# Sheet-ThermalType-STM32.net
KiCad netlist of a schematic drawn in Altium Designer
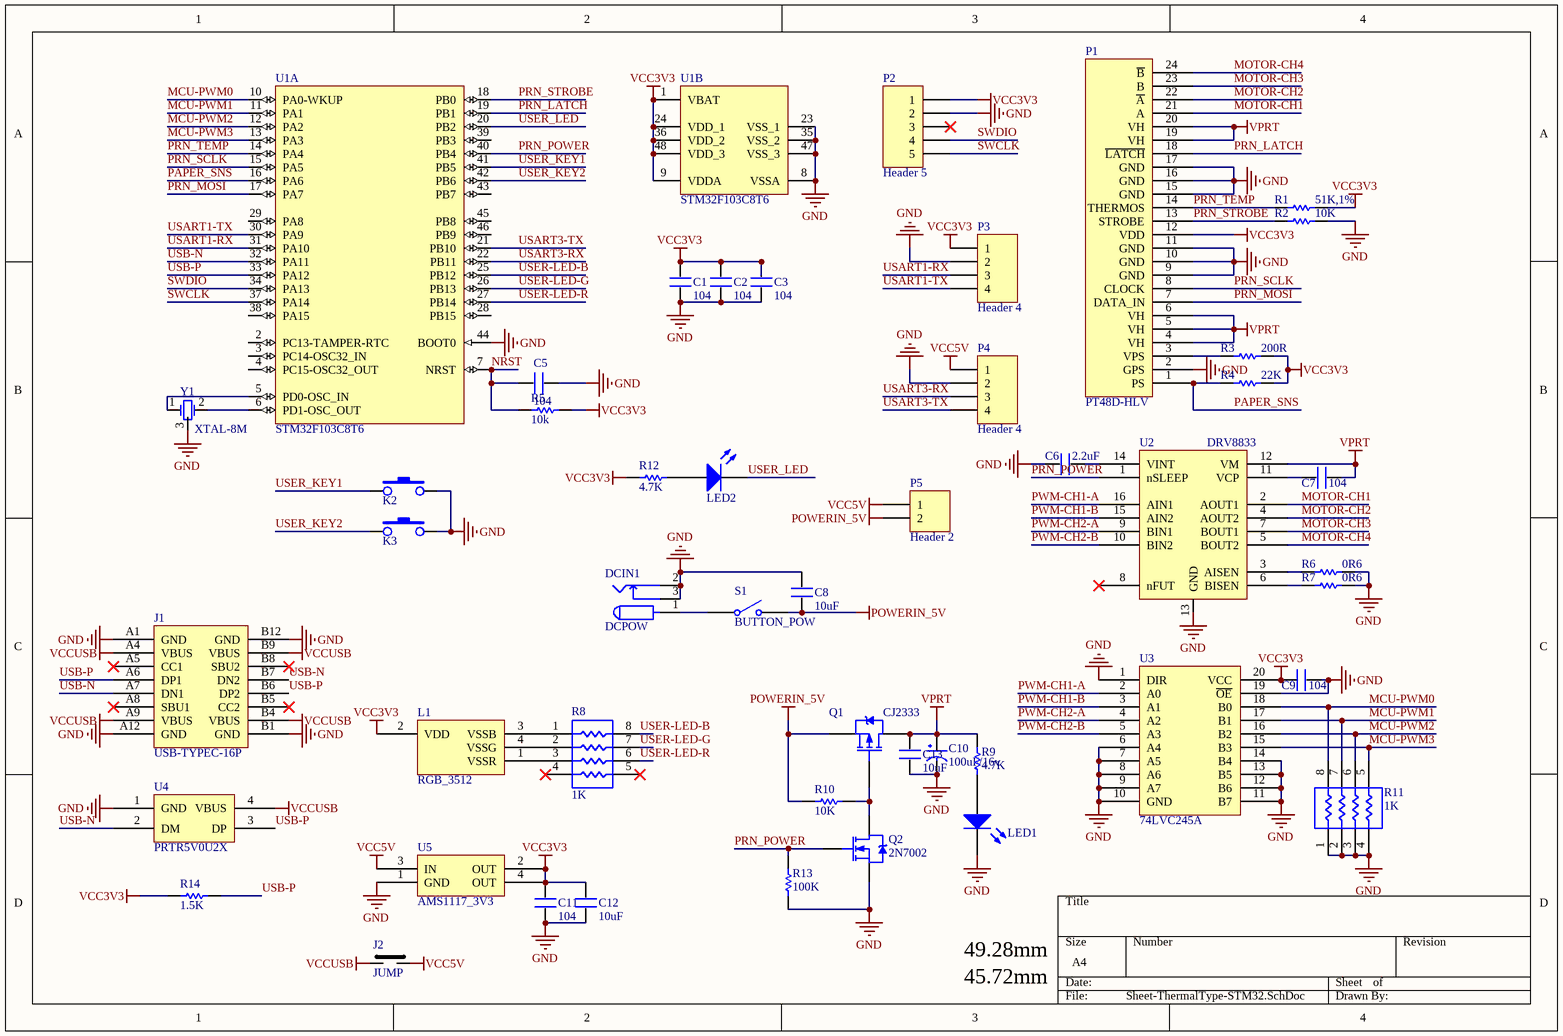
[diagram p0: Sheet-ThermalType-STM32.SchDoc]

(export (version "E")
  (design (tool "Eeschema 10.0.6"))
  (components
    (comp (ref "C1") (value "104") (footprint "0603c") (libsource (lib "Mlia") (part "0603c")))
    (comp (ref "C2") (value "104") (footprint "0603c") (libsource (lib "Mlia") (part "0603c")))
    (comp (ref "C3") (value "104") (footprint "0603c") (libsource (lib "Mlia") (part "0603c")))
    (comp (ref "C5") (value "104") (footprint "0603c") (libsource (lib "Mlia") (part "0603c")))
    (comp (ref "C6")
      (value "2.2uF")
      (footprint "0603C")
      (description "电容")
      (libsource (lib "Mlia") (part "0603C"))
    )
    (comp (ref "C7")
      (value "104")
      (footprint "0603C")
      (description "电容")
      (libsource (lib "Mlia") (part "0603C"))
    )
    (comp (ref "C8") (value "10uF") (footprint "0603C") (libsource (lib "Mlia") (part "0603C")))
    (comp (ref "C9")
      (value "104")
      (footprint "0603C")
      (description "电容")
      (libsource (lib "Mlia") (part "0603C"))
    )
    (comp (ref "C10")
      (value "100uF/16v")
      (footprint "ECAP_V")
      (description "电容")
      (libsource (lib "Mlia") (part "ECAP"))
    )
    (comp (ref "C11") (value "104") (footprint "0603C") (libsource (lib "Mlia") (part "0603C")))
    (comp (ref "C12") (value "10uF") (footprint "0603C") (libsource (lib "Mlia") (part "0603C")))
    (comp (ref "C13") (value "10uF") (footprint "0603C") (libsource (lib "Mlia") (part "0603C")))
    (comp (ref "DCIN1")
      (value "DCPOW")
      (footprint "DC10B")
      (description "DC电源头")
      (libsource (lib "Mlia") (part "DCPOW"))
    )
    (comp (ref "J1")
      (value "USB-TYPEC-16P")
      (footprint "USB-TYPEC-16P")
      (libsource (lib "Mlia") (part "USB-TYPEC-16P"))
    )
    (comp (ref "J2") (value "JUMP") (footprint "JUMP") (libsource (lib "Mlia") (part "JUMP")))
    (comp (ref "K2")
      (value "侧脚6*6*X微动按键")
      (footprint "侧脚6*6*X微动按键")
      (libsource (lib "Mlia") (part "侧脚6*6*X微动按键"))
    )
    (comp (ref "K3")
      (value "侧脚6*6*X微动按键")
      (footprint "侧脚6*6*X微动按键")
      (libsource (lib "Mlia") (part "侧脚6*6*X微动按键"))
    )
    (comp (ref "L1") (value "RGB_3512") (footprint "RGB_3528") (libsource (lib "Mlia") (part "RGB_3512")))
    (comp (ref "LED1") (value "0603LED") (footprint "0603LED") (libsource (lib "Mlia") (part "0603LED")))
    (comp (ref "LED2") (value "0603LED") (footprint "0603LED") (libsource (lib "Mlia") (part "0603LED")))
    (comp (ref "P1")
      (value "PT48D-HLV")
      (footprint "_FPC_24P_0.5MM")
      (libsource (lib "Mlia") (part "PT48D-HLV"))
    )
    (comp (ref "P2")
      (value "Header 5")
      (footprint "sh1.25_LT_5P")
      (description "Header, 5-Pin")
      (fields (field (name "PUBLISHER") "Altium Limited"))
      (libsource (lib "Miscellaneous Connectors") (part "Header 5"))
    )
    (comp (ref "P3")
      (value "Header 4")
      (footprint "SH1.25_LT_4P")
      (description "Header, 4-Pin")
      (fields (field (name "PUBLISHER") "Altium Limited"))
      (libsource (lib "Miscellaneous Connectors") (part "Header 4"))
    )
    (comp (ref "P4")
      (value "Header 4")
      (footprint "SH1.25_LT_4P")
      (description "Header, 4-Pin")
      (fields (field (name "PUBLISHER") "Altium Limited"))
      (libsource (lib "Miscellaneous Connectors") (part "Header 4"))
    )
    (comp (ref "P5")
      (value "Header 2")
      (footprint "HDR1X2")
      (description "Header, 2-Pin")
      (fields (field (name "PUBLISHER") "Altium Limited"))
      (libsource (lib "Miscellaneous Connectors") (part "Header 2"))
    )
    (comp (ref "Q1")
      (value "CJ2333")
      (footprint "CJ2333")
      (description "P-MOS")
      (libsource (lib "Mlia") (part "CJ2333"))
    )
    (comp (ref "Q2")
      (value "2N7002")
      (footprint "2N7002")
      (description "N-Channel Power MOSFET")
      (fields (field (name "PUBLISHER") "Altium Limited"))
      (libsource (lib "Mlia") (part "NMOS-2"))
    )
    (comp (ref "R1")
      (value "51K,1%")
      (footprint "0603r")
      (description "电阻")
      (libsource (lib "Mlia") (part "0603R"))
    )
    (comp (ref "R2")
      (value "10K")
      (footprint "0603r")
      (description "电阻")
      (libsource (lib "Mlia") (part "0603R"))
    )
    (comp (ref "R3")
      (value "200R")
      (footprint "0603r")
      (description "电阻")
      (libsource (lib "Mlia") (part "0603R"))
    )
    (comp (ref "R4")
      (value "22K")
      (footprint "0603r")
      (description "电阻")
      (libsource (lib "Mlia") (part "0603R"))
    )
    (comp (ref "R5") (value "10k") (footprint "0603r") (libsource (lib "Mlia") (part "0603r")))
    (comp (ref "R6")
      (value "0R6")
      (footprint "0805R")
      (description "电阻")
      (libsource (lib "Mlia") (part "0805R"))
    )
    (comp (ref "R7")
      (value "0R6")
      (footprint "0805R")
      (description "电阻")
      (libsource (lib "Mlia") (part "0805R"))
    )
    (comp (ref "R8") (value "1K") (footprint "0603RES") (libsource (lib "Mlia") (part "0603RES")))
    (comp (ref "R9") (value "4.7K") (footprint "0603r") (libsource (lib "Mlia") (part "0603R")))
    (comp (ref "R10")
      (value "10K")
      (footprint "0603r")
      (description "电阻")
      (libsource (lib "Mlia") (part "0603R"))
    )
    (comp (ref "R11")
      (value "1K")
      (footprint "0603RES")
      (description "排阻")
      (libsource (lib "Mlia") (part "0603RES"))
    )
    (comp (ref "R12") (value "4.7K") (footprint "0603r") (libsource (lib "Mlia") (part "0603R")))
    (comp (ref "R13")
      (value "100K")
      (footprint "0603r")
      (description "电阻")
      (libsource (lib "Mlia") (part "0603R"))
    )
    (comp (ref "R14") (value "1.5K") (footprint "0603r") (libsource (lib "Mlia") (part "0603R")))
    (comp (ref "S1") (value "BUTTON_POW") (footprint "拨动开关SS-12D") (libsource (lib "Mlia") (part "自锁开关")))
    (comp (ref "U1")
      (value "STM32F103C8T6")
      (footprint "STM-LQFP48-L")
      (libsource (lib "STMicroelectronics STM32 F1") (part "STM32F103C8T6"))
    )
    (comp (ref "U2") (value "DRV8833") (footprint "DRV8833") (libsource (lib "Mlia") (part "DRV8833")))
    (comp (ref "U3")
      (value "74LVC245A")
      (footprint "Mlia:TSSOP20")
      (description "8通道隔离芯片")
      (libsource (lib "Mlia") (part "74LVC245A"))
    )
    (comp (ref "U4")
      (value "PRTR5V0U2X")
      (footprint "SOT-143")
      (description "超低容值轨对轨静电放电保护二极管,主要保护两条高速数据或者高频率信号线免受静电放电和其他瞬变的影响")
      (libsource (lib "Mlia") (part "PRTR5V0U2X"))
    )
    (comp (ref "U5")
      (value "AMS1117_3V3")
      (footprint "AMS1117_SOT223")
      (libsource (lib "Mlia") (part "AMS1117"))
    )
    (comp (ref "Y1")
      (value "XTAL-8M")
      (footprint "XTAL_8M")
      (description "晶振")
      (libsource (lib "Mlia") (part "XTAL-8M"))
    )
  )
  (nets
    (net (code "1") (name "/MCU-PWM0") (class "Default")
      (node (ref "R11") (pin "8") (pinfunction "8_8") (pintype "passive"))
      (node (ref "U1") (pin "10") (pinfunction "PA0-WKUP_10") (pintype "bidirectional"))
      (node (ref "U3") (pin "18") (pinfunction "B0_18") (pintype "passive"))
    )
    (net (code "2") (name "/MCU-PWM1") (class "Default")
      (node (ref "R11") (pin "7") (pinfunction "7_7") (pintype "passive"))
      (node (ref "U1") (pin "11") (pinfunction "PA1_11") (pintype "bidirectional"))
      (node (ref "U3") (pin "17") (pinfunction "B1_17") (pintype "passive"))
    )
    (net (code "3") (name "/MCU-PWM2") (class "Default")
      (node (ref "R11") (pin "6") (pinfunction "6_6") (pintype "passive"))
      (node (ref "U1") (pin "12") (pinfunction "PA2_12") (pintype "bidirectional"))
      (node (ref "U3") (pin "16") (pinfunction "B2_16") (pintype "passive"))
    )
    (net (code "4") (name "/MCU-PWM3") (class "Default")
      (node (ref "R11") (pin "5") (pinfunction "5_5") (pintype "passive"))
      (node (ref "U1") (pin "13") (pinfunction "PA3_13") (pintype "bidirectional"))
      (node (ref "U3") (pin "15") (pinfunction "B3_15") (pintype "passive"))
    )
    (net (code "5") (name "/MOTOR-CH1") (class "Default")
      (node (ref "P1") (pin "21") (pinfunction "A_21") (pintype "passive"))
      (node (ref "U2") (pin "2") (pinfunction "AOUT1_2") (pintype "passive"))
    )
    (net (code "6") (name "/MOTOR-CH2") (class "Default")
      (node (ref "P1") (pin "22") (pinfunction "~{A}_22") (pintype "passive"))
      (node (ref "U2") (pin "4") (pinfunction "AOUT2_4") (pintype "passive"))
    )
    (net (code "7") (name "/MOTOR-CH3") (class "Default")
      (node (ref "P1") (pin "23") (pinfunction "B_23") (pintype "passive"))
      (node (ref "U2") (pin "7") (pinfunction "BOUT1_7") (pintype "passive"))
    )
    (net (code "8") (name "/MOTOR-CH4") (class "Default")
      (node (ref "P1") (pin "24") (pinfunction "~{B}_24") (pintype "passive"))
      (node (ref "U2") (pin "5") (pinfunction "BOUT2_5") (pintype "passive"))
    )
    (net (code "9") (name "/NRST") (class "Default")
      (node (ref "C5") (pin "1") (pintype "passive"))
      (node (ref "R5") (pin "1") (pinfunction "1_1") (pintype "passive"))
      (node (ref "U1") (pin "7") (pinfunction "NRST_7") (pintype "bidirectional"))
    )
    (net (code "10") (name "/PAPER_SNS") (class "Default")
      (node (ref "P1") (pin "1") (pinfunction "PS_1") (pintype "passive"))
      (node (ref "R4") (pin "1") (pinfunction "1_1") (pintype "passive"))
      (node (ref "U1") (pin "16") (pinfunction "PA6_16") (pintype "bidirectional"))
    )
    (net (code "11") (name "/PRN_LATCH") (class "Default")
      (node (ref "P1") (pin "18") (pinfunction "~{LATCH}_18") (pintype "passive"))
      (node (ref "U1") (pin "19") (pinfunction "PB1_19") (pintype "bidirectional"))
    )
    (net (code "12") (name "/PRN_MOSI") (class "Default")
      (node (ref "P1") (pin "7") (pinfunction "DATA_IN_7") (pintype "passive"))
      (node (ref "U1") (pin "17") (pinfunction "PA7_17") (pintype "bidirectional"))
    )
    (net (code "13") (name "/PRN_POWER") (class "Default")
      (node (ref "Q2") (pin "1") (pinfunction "G_1") (pintype "passive"))
      (node (ref "R13") (pin "2") (pinfunction "2_2") (pintype "passive"))
      (node (ref "U1") (pin "40") (pinfunction "PB4_40") (pintype "bidirectional"))
      (node (ref "U2") (pin "1") (pinfunction "nSLEEP_1") (pintype "passive"))
    )
    (net (code "14") (name "/PRN_SCLK") (class "Default")
      (node (ref "P1") (pin "8") (pinfunction "CLOCK_8") (pintype "passive"))
      (node (ref "U1") (pin "15") (pinfunction "PA5_15") (pintype "bidirectional"))
    )
    (net (code "15") (name "/PRN_STROBE") (class "Default")
      (node (ref "P1") (pin "13") (pinfunction "STROBE_13") (pintype "passive"))
      (node (ref "R2") (pin "1") (pinfunction "1_1") (pintype "passive"))
      (node (ref "U1") (pin "18") (pinfunction "PB0_18") (pintype "bidirectional"))
    )
    (net (code "16") (name "/PRN_TEMP") (class "Default")
      (node (ref "P1") (pin "14") (pinfunction "THERMOS_14") (pintype "passive"))
      (node (ref "R1") (pin "1") (pinfunction "1_1") (pintype "passive"))
      (node (ref "U1") (pin "14") (pinfunction "PA4_14") (pintype "bidirectional"))
    )
    (net (code "17") (name "/PWM-CH1-A") (class "Default")
      (node (ref "U2") (pin "16") (pinfunction "AIN1_16") (pintype "passive"))
      (node (ref "U3") (pin "2") (pinfunction "A0_2") (pintype "passive"))
    )
    (net (code "18") (name "/PWM-CH1-B") (class "Default")
      (node (ref "U2") (pin "15") (pinfunction "AIN2_15") (pintype "passive"))
      (node (ref "U3") (pin "3") (pinfunction "A1_3") (pintype "passive"))
    )
    (net (code "19") (name "/PWM-CH2-A") (class "Default")
      (node (ref "U2") (pin "9") (pinfunction "BIN1_9") (pintype "passive"))
      (node (ref "U3") (pin "4") (pinfunction "A2_4") (pintype "passive"))
    )
    (net (code "20") (name "/PWM-CH2-B") (class "Default")
      (node (ref "U2") (pin "10") (pinfunction "BIN2_10") (pintype "passive"))
      (node (ref "U3") (pin "5") (pinfunction "A3_5") (pintype "passive"))
    )
    (net (code "21") (name "/SWCLK") (class "Default")
      (node (ref "P2") (pin "5") (pinfunction "5_5") (pintype "passive"))
      (node (ref "U1") (pin "37") (pinfunction "PA14_37") (pintype "bidirectional"))
    )
    (net (code "22") (name "/SWDIO") (class "Default")
      (node (ref "P2") (pin "4") (pinfunction "4_4") (pintype "passive"))
      (node (ref "U1") (pin "34") (pinfunction "PA13_34") (pintype "bidirectional"))
    )
    (net (code "23") (name "/USART1-RX") (class "Default")
      (node (ref "P3") (pin "3") (pinfunction "3_3") (pintype "passive"))
      (node (ref "U1") (pin "31") (pinfunction "PA10_31") (pintype "bidirectional"))
    )
    (net (code "24") (name "/USART1-TX") (class "Default")
      (node (ref "P3") (pin "4") (pinfunction "4_4") (pintype "passive"))
      (node (ref "U1") (pin "30") (pinfunction "PA9_30") (pintype "bidirectional"))
    )
    (net (code "25") (name "/USART3-RX") (class "Default")
      (node (ref "P4") (pin "3") (pinfunction "3_3") (pintype "passive"))
      (node (ref "U1") (pin "22") (pinfunction "PB11_22") (pintype "bidirectional"))
    )
    (net (code "26") (name "/USART3-TX") (class "Default")
      (node (ref "P4") (pin "4") (pinfunction "4_4") (pintype "passive"))
      (node (ref "U1") (pin "21") (pinfunction "PB10_21") (pintype "bidirectional"))
    )
    (net (code "27") (name "/USB-N") (class "Default")
      (node (ref "J1") (pin "A7") (pinfunction "DN1_A7") (pintype "passive"))
      (node (ref "J1") (pin "B7") (pinfunction "DN2_B7") (pintype "passive"))
      (node (ref "U1") (pin "32") (pinfunction "PA11_32") (pintype "bidirectional"))
      (node (ref "U4") (pin "2") (pinfunction "DM_2") (pintype "passive"))
    )
    (net (code "28") (name "/USB-P") (class "Default")
      (node (ref "J1") (pin "A6") (pinfunction "DP1_A6") (pintype "passive"))
      (node (ref "J1") (pin "B6") (pinfunction "DP2_B6") (pintype "passive"))
      (node (ref "R14") (pin "2") (pinfunction "2_2") (pintype "passive"))
      (node (ref "U1") (pin "33") (pinfunction "PA12_33") (pintype "bidirectional"))
      (node (ref "U4") (pin "3") (pinfunction "DP_3") (pintype "passive"))
    )
    (net (code "29") (name "/USER-LED-B") (class "Default")
      (node (ref "R8") (pin "8") (pinfunction "8_8") (pintype "passive"))
      (node (ref "U1") (pin "25") (pinfunction "PB12_25") (pintype "bidirectional"))
    )
    (net (code "30") (name "/USER-LED-G") (class "Default")
      (node (ref "R8") (pin "7") (pinfunction "7_7") (pintype "passive"))
      (node (ref "U1") (pin "26") (pinfunction "PB13_26") (pintype "bidirectional"))
    )
    (net (code "31") (name "/USER-LED-R") (class "Default")
      (node (ref "R8") (pin "6") (pinfunction "6_6") (pintype "passive"))
      (node (ref "U1") (pin "27") (pinfunction "PB14_27") (pintype "bidirectional"))
    )
    (net (code "32") (name "/USER_KEY1") (class "Default")
      (node (ref "K2") (pin "2") (pinfunction "2_2") (pintype "passive"))
      (node (ref "U1") (pin "41") (pinfunction "PB5_41") (pintype "bidirectional"))
    )
    (net (code "33") (name "/USER_KEY2") (class "Default")
      (node (ref "K3") (pin "2") (pinfunction "2_2") (pintype "passive"))
      (node (ref "U1") (pin "42") (pinfunction "PB6_42") (pintype "bidirectional"))
    )
    (net (code "34") (name "/USER_LED") (class "Default")
      (node (ref "LED2") (pin "2") (pinfunction "K_2") (pintype "passive"))
      (node (ref "U1") (pin "20") (pinfunction "PB2_20") (pintype "bidirectional"))
    )
    (net (code "35") (name "GND") (class "Default")
      (node (ref "C1") (pin "1") (pintype "passive"))
      (node (ref "C10") (pin "2") (pinfunction "GND_2") (pintype "passive"))
      (node (ref "C11") (pin "1") (pintype "passive"))
      (node (ref "C12") (pin "1") (pintype "passive"))
      (node (ref "C13") (pin "1") (pintype "passive"))
      (node (ref "C2") (pin "1") (pintype "passive"))
      (node (ref "C3") (pin "1") (pintype "passive"))
      (node (ref "C5") (pin "2") (pintype "passive"))
      (node (ref "C6") (pin "1") (pintype "passive"))
      (node (ref "C8") (pin "2") (pintype "passive"))
      (node (ref "C9") (pin "2") (pintype "passive"))
      (node (ref "DCIN1") (pin "2") (pintype "passive"))
      (node (ref "DCIN1") (pin "3") (pintype "passive"))
      (node (ref "J1") (pin "A1") (pinfunction "GND_A1") (pintype "passive"))
      (node (ref "J1") (pin "A12") (pinfunction "GND_A12") (pintype "passive"))
      (node (ref "J1") (pin "B1") (pinfunction "GND_B1") (pintype "passive"))
      (node (ref "J1") (pin "B12") (pinfunction "GND_B12") (pintype "passive"))
      (node (ref "K2") (pin "1") (pinfunction "1_1") (pintype "passive"))
      (node (ref "K3") (pin "1") (pinfunction "1_1") (pintype "passive"))
      (node (ref "LED1") (pin "2") (pinfunction "K_2") (pintype "passive"))
      (node (ref "P1") (pin "10") (pinfunction "GND_10") (pintype "passive"))
      (node (ref "P1") (pin "11") (pinfunction "GND_11") (pintype "passive"))
      (node (ref "P1") (pin "15") (pinfunction "GND_15") (pintype "passive"))
      (node (ref "P1") (pin "16") (pinfunction "GND_16") (pintype "passive"))
      (node (ref "P1") (pin "17") (pinfunction "GND_17") (pintype "passive"))
      (node (ref "P1") (pin "2") (pinfunction "GPS_2") (pintype "passive"))
      (node (ref "P1") (pin "9") (pinfunction "GND_9") (pintype "passive"))
      (node (ref "P2") (pin "2") (pinfunction "2_2") (pintype "passive"))
      (node (ref "P3") (pin "2") (pinfunction "2_2") (pintype "passive"))
      (node (ref "P4") (pin "2") (pinfunction "2_2") (pintype "passive"))
      (node (ref "Q2") (pin "2") (pinfunction "S_2") (pintype "passive"))
      (node (ref "R11") (pin "1") (pinfunction "1_1") (pintype "passive"))
      (node (ref "R11") (pin "2") (pinfunction "2_2") (pintype "passive"))
      (node (ref "R11") (pin "3") (pinfunction "3_3") (pintype "passive"))
      (node (ref "R11") (pin "4") (pinfunction "4_4") (pintype "passive"))
      (node (ref "R13") (pin "1") (pinfunction "1_1") (pintype "passive"))
      (node (ref "R2") (pin "2") (pinfunction "2_2") (pintype "passive"))
      (node (ref "R6") (pin "2") (pinfunction "2_2") (pintype "passive"))
      (node (ref "R7") (pin "2") (pinfunction "2_2") (pintype "passive"))
      (node (ref "U1") (pin "23") (pinfunction "VSS_1_23") (pintype "power_in"))
      (node (ref "U1") (pin "35") (pinfunction "VSS_2_35") (pintype "power_in"))
      (node (ref "U1") (pin "44") (pinfunction "BOOT0_44") (pintype "input"))
      (node (ref "U1") (pin "47") (pinfunction "VSS_3_47") (pintype "power_in"))
      (node (ref "U1") (pin "8") (pinfunction "VSSA_8") (pintype "power_in"))
      (node (ref "U2") (pin "13") (pinfunction "GND_13") (pintype "passive"))
      (node (ref "U3") (pin "1") (pinfunction "DIR_1") (pintype "passive"))
      (node (ref "U3") (pin "10") (pinfunction "GND_10") (pintype "passive"))
      (node (ref "U3") (pin "11") (pinfunction "B7_11") (pintype "passive"))
      (node (ref "U3") (pin "12") (pinfunction "B6_12") (pintype "passive"))
      (node (ref "U3") (pin "13") (pinfunction "B5_13") (pintype "passive"))
      (node (ref "U3") (pin "14") (pinfunction "B4_14") (pintype "passive"))
      (node (ref "U3") (pin "19") (pinfunction "~{OE}_19") (pintype "passive"))
      (node (ref "U3") (pin "6") (pinfunction "A4_6") (pintype "passive"))
      (node (ref "U3") (pin "7") (pinfunction "A5_7") (pintype "passive"))
      (node (ref "U3") (pin "8") (pinfunction "A6_8") (pintype "passive"))
      (node (ref "U3") (pin "9") (pinfunction "A7_9") (pintype "passive"))
      (node (ref "U4") (pin "1") (pinfunction "GND_1") (pintype "passive"))
      (node (ref "U5") (pin "1") (pinfunction "GND_1") (pintype "passive"))
      (node (ref "Y1") (pin "3") (pinfunction "3_3") (pintype "passive"))
    )
    (net (code "36") (name "Net-(L1-VSSB)") (class "Default")
      (node (ref "L1") (pin "3") (pinfunction "VSSB_3") (pintype "passive"))
      (node (ref "R8") (pin "1") (pinfunction "1_1") (pintype "passive"))
    )
    (net (code "37") (name "Net-(L1-VSSG)") (class "Default")
      (node (ref "L1") (pin "4") (pinfunction "VSSG_4") (pintype "passive"))
      (node (ref "R8") (pin "2") (pinfunction "2_2") (pintype "passive"))
    )
    (net (code "38") (name "Net-(L1-VSSR)") (class "Default")
      (node (ref "L1") (pin "1") (pinfunction "VSSR_1") (pintype "passive"))
      (node (ref "R8") (pin "3") (pinfunction "3_3") (pintype "passive"))
    )
    (net (code "39") (name "Net-(LED1-A)") (class "Default")
      (node (ref "LED1") (pin "1") (pinfunction "A_1") (pintype "passive"))
      (node (ref "R9") (pin "1") (pinfunction "1_1") (pintype "passive"))
    )
    (net (code "40") (name "Net-(LED2-A)") (class "Default")
      (node (ref "LED2") (pin "1") (pinfunction "A_1") (pintype "passive"))
      (node (ref "R12") (pin "1") (pinfunction "1_1") (pintype "passive"))
    )
    (net (code "41") (name "Net-(P1-VPS)") (class "Default")
      (node (ref "P1") (pin "3") (pinfunction "VPS_3") (pintype "passive"))
      (node (ref "R3") (pin "1") (pinfunction "1_1") (pintype "passive"))
    )
    (net (code "42") (name "Net-(Q1-G)") (class "Default")
      (node (ref "Q1") (pin "1") (pinfunction "G_1") (pintype "passive"))
      (node (ref "Q2") (pin "3") (pinfunction "D_3") (pintype "passive"))
      (node (ref "R10") (pin "2") (pinfunction "2_2") (pintype "passive"))
    )
    (net (code "43") (name "Net-(S1-COMMON)") (class "Default")
      (node (ref "DCIN1") (pin "1") (pintype "passive"))
      (node (ref "S1") (pin "2") (pinfunction "COMMON_2") (pintype "passive"))
    )
    (net (code "44") (name "Net-(U1A-PD0-OSC_IN)") (class "Default")
      (node (ref "U1") (pin "5") (pinfunction "PD0-OSC_IN_5") (pintype "bidirectional"))
      (node (ref "Y1") (pin "1") (pinfunction "OSC1_1") (pintype "passive"))
    )
    (net (code "45") (name "Net-(U1A-PD1-OSC_OUT)") (class "Default")
      (node (ref "U1") (pin "6") (pinfunction "PD1-OSC_OUT_6") (pintype "bidirectional"))
      (node (ref "Y1") (pin "2") (pinfunction "OSC2_2") (pintype "passive"))
    )
    (net (code "46") (name "Net-(U2-AISEN)") (class "Default")
      (node (ref "R6") (pin "1") (pinfunction "1_1") (pintype "passive"))
      (node (ref "U2") (pin "3") (pinfunction "AISEN_3") (pintype "passive"))
    )
    (net (code "47") (name "Net-(U2-BISEN)") (class "Default")
      (node (ref "R7") (pin "1") (pinfunction "1_1") (pintype "passive"))
      (node (ref "U2") (pin "6") (pinfunction "BISEN_6") (pintype "passive"))
    )
    (net (code "48") (name "Net-(U2-VCP)") (class "Default")
      (node (ref "C7") (pin "1") (pintype "passive"))
      (node (ref "U2") (pin "11") (pinfunction "VCP_11") (pintype "passive"))
    )
    (net (code "49") (name "Net-(U2-VINT)") (class "Default")
      (node (ref "C6") (pin "2") (pintype "passive"))
      (node (ref "U2") (pin "14") (pinfunction "VINT_14") (pintype "passive"))
    )
    (net (code "50") (name "POWERIN_5V") (class "Default")
      (node (ref "C8") (pin "1") (pintype "passive"))
      (node (ref "P5") (pin "2") (pinfunction "2_2") (pintype "passive"))
      (node (ref "Q1") (pin "3") (pinfunction "S_3") (pintype "passive"))
      (node (ref "R10") (pin "1") (pinfunction "1_1") (pintype "passive"))
      (node (ref "S1") (pin "3") (pinfunction "NO_3") (pintype "passive"))
    )
    (net (code "51") (name "VCC3V3") (class "Default")
      (node (ref "C1") (pin "2") (pintype "passive"))
      (node (ref "C11") (pin "2") (pintype "passive"))
      (node (ref "C12") (pin "2") (pintype "passive"))
      (node (ref "C2") (pin "2") (pintype "passive"))
      (node (ref "C3") (pin "2") (pintype "passive"))
      (node (ref "C9") (pin "1") (pintype "passive"))
      (node (ref "L1") (pin "2") (pinfunction "VDD_2") (pintype "passive"))
      (node (ref "P1") (pin "12") (pinfunction "VDD_12") (pintype "passive"))
      (node (ref "P2") (pin "1") (pinfunction "1_1") (pintype "passive"))
      (node (ref "P3") (pin "1") (pinfunction "1_1") (pintype "passive"))
      (node (ref "R1") (pin "2") (pinfunction "2_2") (pintype "passive"))
      (node (ref "R12") (pin "2") (pinfunction "2_2") (pintype "passive"))
      (node (ref "R14") (pin "1") (pinfunction "1_1") (pintype "passive"))
      (node (ref "R3") (pin "2") (pinfunction "2_2") (pintype "passive"))
      (node (ref "R4") (pin "2") (pinfunction "2_2") (pintype "passive"))
      (node (ref "R5") (pin "2") (pinfunction "2_2") (pintype "passive"))
      (node (ref "U1") (pin "1") (pinfunction "VBAT_1") (pintype "power_in"))
      (node (ref "U1") (pin "24") (pinfunction "VDD_1_24") (pintype "power_in"))
      (node (ref "U1") (pin "36") (pinfunction "VDD_2_36") (pintype "power_in"))
      (node (ref "U1") (pin "48") (pinfunction "VDD_3_48") (pintype "power_in"))
      (node (ref "U1") (pin "9") (pinfunction "VDDA_9") (pintype "power_in"))
      (node (ref "U3") (pin "20") (pinfunction "VCC_20") (pintype "passive"))
      (node (ref "U5") (pin "2") (pinfunction "OUT_2") (pintype "passive"))
      (node (ref "U5") (pin "4") (pinfunction "OUT_4") (pintype "passive"))
    )
    (net (code "52") (name "VCC5V") (class "Default")
      (node (ref "J2") (pin "2") (pinfunction "2_2") (pintype "passive"))
      (node (ref "P4") (pin "1") (pinfunction "1_1") (pintype "passive"))
      (node (ref "P5") (pin "1") (pinfunction "1_1") (pintype "passive"))
      (node (ref "U5") (pin "3") (pinfunction "IN_3") (pintype "passive"))
    )
    (net (code "53") (name "VCCUSB") (class "Default")
      (node (ref "J1") (pin "A4") (pinfunction "VBUS_A4") (pintype "passive"))
      (node (ref "J1") (pin "A9") (pinfunction "VBUS_A9") (pintype "passive"))
      (node (ref "J1") (pin "B4") (pinfunction "VBUS_B4") (pintype "passive"))
      (node (ref "J1") (pin "B9") (pinfunction "VBUS_B9") (pintype "passive"))
      (node (ref "J2") (pin "1") (pinfunction "1_1") (pintype "passive"))
      (node (ref "U4") (pin "4") (pinfunction "VBUS_4") (pintype "passive"))
    )
    (net (code "54") (name "VPRT") (class "Default")
      (node (ref "C10") (pin "1") (pinfunction "VCC_1") (pintype "passive"))
      (node (ref "C13") (pin "2") (pintype "passive"))
      (node (ref "C7") (pin "2") (pintype "passive"))
      (node (ref "P1") (pin "19") (pinfunction "VH_19") (pintype "passive"))
      (node (ref "P1") (pin "20") (pinfunction "VH_20") (pintype "passive"))
      (node (ref "P1") (pin "4") (pinfunction "VH_4") (pintype "passive"))
      (node (ref "P1") (pin "5") (pinfunction "VH_5") (pintype "passive"))
      (node (ref "P1") (pin "6") (pinfunction "VH_6") (pintype "passive"))
      (node (ref "Q1") (pin "2") (pinfunction "D_2") (pintype "passive"))
      (node (ref "R9") (pin "2") (pinfunction "2_2") (pintype "passive"))
      (node (ref "U2") (pin "12") (pinfunction "VM_12") (pintype "passive"))
    )
    (net (code "55") (name "unconnected-(J1-CC1-PadA5)") (class "Default")
      (node (ref "J1") (pin "A5") (pinfunction "CC1_A5") (pintype "passive+no_connect"))
    )
    (net (code "56") (name "unconnected-(J1-CC2-PadB5)") (class "Default")
      (node (ref "J1") (pin "B5") (pinfunction "CC2_B5") (pintype "passive+no_connect"))
    )
    (net (code "57") (name "unconnected-(J1-SBU1-PadA8)") (class "Default")
      (node (ref "J1") (pin "A8") (pinfunction "SBU1_A8") (pintype "passive+no_connect"))
    )
    (net (code "58") (name "unconnected-(J1-SBU2-PadB8)") (class "Default")
      (node (ref "J1") (pin "B8") (pinfunction "SBU2_B8") (pintype "passive+no_connect"))
    )
    (net (code "59") (name "unconnected-(P2-Pad3)") (class "Default")
      (node (ref "P2") (pin "3") (pinfunction "3_3") (pintype "passive+no_connect"))
    )
    (net (code "60") (name "unconnected-(R8-Pad4)") (class "Default")
      (node (ref "R8") (pin "4") (pinfunction "4_4") (pintype "passive+no_connect"))
    )
    (net (code "61") (name "unconnected-(R8-Pad5)") (class "Default")
      (node (ref "R8") (pin "5") (pinfunction "5_5") (pintype "passive+no_connect"))
    )
    (net (code "62") (name "unconnected-(U1A-PA8-Pad29)") (class "Default")
      (node (ref "U1") (pin "29") (pinfunction "PA8_29") (pintype "bidirectional"))
    )
    (net (code "63") (name "unconnected-(U1A-PA15-Pad38)") (class "Default")
      (node (ref "U1") (pin "38") (pinfunction "PA15_38") (pintype "bidirectional"))
    )
    (net (code "64") (name "unconnected-(U1A-PB3-Pad39)") (class "Default")
      (node (ref "U1") (pin "39") (pinfunction "PB3_39") (pintype "bidirectional"))
    )
    (net (code "65") (name "unconnected-(U1A-PB7-Pad43)") (class "Default")
      (node (ref "U1") (pin "43") (pinfunction "PB7_43") (pintype "bidirectional"))
    )
    (net (code "66") (name "unconnected-(U1A-PB8-Pad45)") (class "Default")
      (node (ref "U1") (pin "45") (pinfunction "PB8_45") (pintype "bidirectional"))
    )
    (net (code "67") (name "unconnected-(U1A-PB9-Pad46)") (class "Default")
      (node (ref "U1") (pin "46") (pinfunction "PB9_46") (pintype "bidirectional"))
    )
    (net (code "68") (name "unconnected-(U1A-PB15-Pad28)") (class "Default")
      (node (ref "U1") (pin "28") (pinfunction "PB15_28") (pintype "bidirectional"))
    )
    (net (code "69") (name "unconnected-(U1A-PC13-TAMPER-RTC-Pad2)") (class "Default")
      (node (ref "U1") (pin "2") (pinfunction "PC13-TAMPER-RTC_2") (pintype "bidirectional"))
    )
    (net (code "70") (name "unconnected-(U1A-PC14-OSC32_IN-Pad3)") (class "Default")
      (node (ref "U1") (pin "3") (pinfunction "PC14-OSC32_IN_3") (pintype "bidirectional"))
    )
    (net (code "71") (name "unconnected-(U1A-PC15-OSC32_OUT-Pad4)") (class "Default")
      (node (ref "U1") (pin "4") (pinfunction "PC15-OSC32_OUT_4") (pintype "bidirectional"))
    )
    (net (code "72") (name "unconnected-(U2-nFUT-Pad8)") (class "Default")
      (node (ref "U2") (pin "8") (pinfunction "nFUT_8") (pintype "passive+no_connect"))
    )
  )
)
